# Chov2_led.net
KiCad netlist of a schematic drawn in Altium Designer
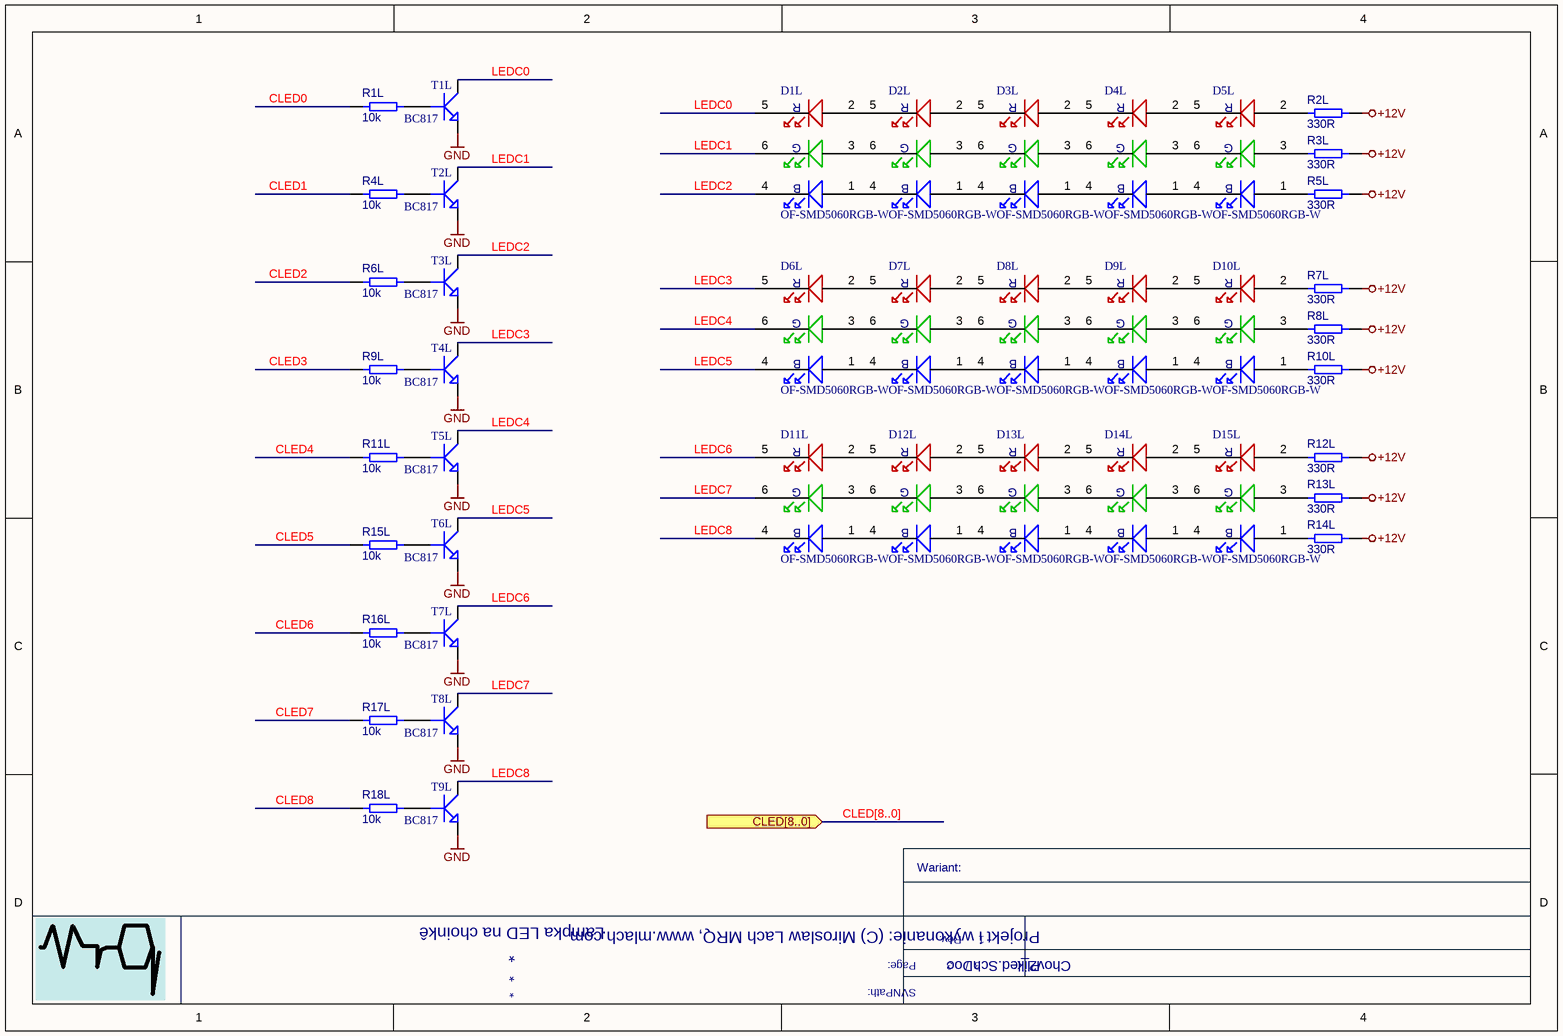
[diagram p0: Chov2_led.SchDoc]

(export (version "E")
  (design (tool "Eeschema 10.0.6"))
  (components
    (comp (ref "D1L")
      (value "OF-SMD5060RGB-W")
      (footprint "OF-SMD5060RGB-W")
      (libsource (lib "Parts") (part "OF-SMD5060RGB-W"))
    )
    (comp (ref "D2L")
      (value "OF-SMD5060RGB-W")
      (footprint "OF-SMD5060RGB-W")
      (libsource (lib "Parts") (part "OF-SMD5060RGB-W"))
    )
    (comp (ref "D3L")
      (value "OF-SMD5060RGB-W")
      (footprint "OF-SMD5060RGB-W")
      (libsource (lib "Parts") (part "OF-SMD5060RGB-W"))
    )
    (comp (ref "D4L")
      (value "OF-SMD5060RGB-W")
      (footprint "OF-SMD5060RGB-W")
      (libsource (lib "Parts") (part "OF-SMD5060RGB-W"))
    )
    (comp (ref "D5L")
      (value "OF-SMD5060RGB-W")
      (footprint "OF-SMD5060RGB-W")
      (libsource (lib "Parts") (part "OF-SMD5060RGB-W"))
    )
    (comp (ref "D6L")
      (value "OF-SMD5060RGB-W")
      (footprint "OF-SMD5060RGB-W")
      (libsource (lib "Parts") (part "OF-SMD5060RGB-W"))
    )
    (comp (ref "D7L")
      (value "OF-SMD5060RGB-W")
      (footprint "OF-SMD5060RGB-W")
      (libsource (lib "Parts") (part "OF-SMD5060RGB-W"))
    )
    (comp (ref "D8L")
      (value "OF-SMD5060RGB-W")
      (footprint "OF-SMD5060RGB-W")
      (libsource (lib "Parts") (part "OF-SMD5060RGB-W"))
    )
    (comp (ref "D9L")
      (value "OF-SMD5060RGB-W")
      (footprint "OF-SMD5060RGB-W")
      (libsource (lib "Parts") (part "OF-SMD5060RGB-W"))
    )
    (comp (ref "D10L")
      (value "OF-SMD5060RGB-W")
      (footprint "OF-SMD5060RGB-W")
      (libsource (lib "Parts") (part "OF-SMD5060RGB-W"))
    )
    (comp (ref "D11L")
      (value "OF-SMD5060RGB-W")
      (footprint "OF-SMD5060RGB-W")
      (libsource (lib "Parts") (part "OF-SMD5060RGB-W"))
    )
    (comp (ref "D12L")
      (value "OF-SMD5060RGB-W")
      (footprint "OF-SMD5060RGB-W")
      (libsource (lib "Parts") (part "OF-SMD5060RGB-W"))
    )
    (comp (ref "D13L")
      (value "OF-SMD5060RGB-W")
      (footprint "OF-SMD5060RGB-W")
      (libsource (lib "Parts") (part "OF-SMD5060RGB-W"))
    )
    (comp (ref "D14L")
      (value "OF-SMD5060RGB-W")
      (footprint "OF-SMD5060RGB-W")
      (libsource (lib "Parts") (part "OF-SMD5060RGB-W"))
    )
    (comp (ref "D15L")
      (value "OF-SMD5060RGB-W")
      (footprint "OF-SMD5060RGB-W")
      (libsource (lib "Parts") (part "OF-SMD5060RGB-W"))
    )
    (comp (ref "R1L")
      (value "0603WGF10KT5E")
      (footprint "0603-IPC")
      (fields (field (name "OTHERPARAMS") "10k") (field (name "TOLERANCE") "1%"))
      (libsource (lib "Parts") (part "R"))
    )
    (comp (ref "R2L")
      (value "0805S8F3300T5E")
      (footprint "0805")
      (fields (field (name "OTHERPARAMS") "330R") (field (name "TOLERANCE") "1%"))
      (libsource (lib "Parts") (part "R"))
    )
    (comp (ref "R3L")
      (value "0805S8F3300T5E")
      (footprint "0805")
      (fields (field (name "OTHERPARAMS") "330R") (field (name "TOLERANCE") "1%"))
      (libsource (lib "Parts") (part "R"))
    )
    (comp (ref "R4L")
      (value "0603WGF10KT5E")
      (footprint "0603-IPC")
      (fields (field (name "OTHERPARAMS") "10k") (field (name "TOLERANCE") "1%"))
      (libsource (lib "Parts") (part "R"))
    )
    (comp (ref "R5L")
      (value "0805S8F3300T5E")
      (footprint "0805")
      (fields (field (name "OTHERPARAMS") "330R") (field (name "TOLERANCE") "1%"))
      (libsource (lib "Parts") (part "R"))
    )
    (comp (ref "R6L")
      (value "0603WGF10KT5E")
      (footprint "0603-IPC")
      (fields (field (name "OTHERPARAMS") "10k") (field (name "TOLERANCE") "1%"))
      (libsource (lib "Parts") (part "R"))
    )
    (comp (ref "R7L")
      (value "0805S8F3300T5E")
      (footprint "0805")
      (fields (field (name "OTHERPARAMS") "330R") (field (name "TOLERANCE") "1%"))
      (libsource (lib "Parts") (part "R"))
    )
    (comp (ref "R8L")
      (value "0805S8F3300T5E")
      (footprint "0805")
      (fields (field (name "OTHERPARAMS") "330R") (field (name "TOLERANCE") "1%"))
      (libsource (lib "Parts") (part "R"))
    )
    (comp (ref "R9L")
      (value "0603WGF10KT5E")
      (footprint "0603-IPC")
      (fields (field (name "OTHERPARAMS") "10k") (field (name "TOLERANCE") "1%"))
      (libsource (lib "Parts") (part "R"))
    )
    (comp (ref "R10L")
      (value "0805S8F3300T5E")
      (footprint "0805")
      (fields (field (name "OTHERPARAMS") "330R") (field (name "TOLERANCE") "1%"))
      (libsource (lib "Parts") (part "R"))
    )
    (comp (ref "R11L")
      (value "0603WGF10KT5E")
      (footprint "0603-IPC")
      (fields (field (name "OTHERPARAMS") "10k") (field (name "TOLERANCE") "1%"))
      (libsource (lib "Parts") (part "R"))
    )
    (comp (ref "R12L")
      (value "0805S8F3300T5E")
      (footprint "0805")
      (fields (field (name "OTHERPARAMS") "330R") (field (name "TOLERANCE") "1%"))
      (libsource (lib "Parts") (part "R"))
    )
    (comp (ref "R13L")
      (value "0805S8F3300T5E")
      (footprint "0805")
      (fields (field (name "OTHERPARAMS") "330R") (field (name "TOLERANCE") "1%"))
      (libsource (lib "Parts") (part "R"))
    )
    (comp (ref "R14L")
      (value "0805S8F3300T5E")
      (footprint "0805")
      (fields (field (name "OTHERPARAMS") "330R") (field (name "TOLERANCE") "1%"))
      (libsource (lib "Parts") (part "R"))
    )
    (comp (ref "R15L")
      (value "0603WGF10KT5E")
      (footprint "0603-IPC")
      (fields (field (name "OTHERPARAMS") "10k") (field (name "TOLERANCE") "1%"))
      (libsource (lib "Parts") (part "R"))
    )
    (comp (ref "R16L")
      (value "0603WGF10KT5E")
      (footprint "0603-IPC")
      (fields (field (name "OTHERPARAMS") "10k") (field (name "TOLERANCE") "1%"))
      (libsource (lib "Parts") (part "R"))
    )
    (comp (ref "R17L")
      (value "0603WGF10KT5E")
      (footprint "0603-IPC")
      (fields (field (name "OTHERPARAMS") "10k") (field (name "TOLERANCE") "1%"))
      (libsource (lib "Parts") (part "R"))
    )
    (comp (ref "R18L")
      (value "0603WGF10KT5E")
      (footprint "0603-IPC")
      (fields (field (name "OTHERPARAMS") "10k") (field (name "TOLERANCE") "1%"))
      (libsource (lib "Parts") (part "R"))
    )
    (comp (ref "T1L") (value "BC817") (footprint "SOT23-3") (libsource (lib "Parts") (part "NPN_SOT23-3")))
    (comp (ref "T2L") (value "BC817") (footprint "SOT23-3") (libsource (lib "Parts") (part "NPN_SOT23-3")))
    (comp (ref "T3L") (value "BC817") (footprint "SOT23-3") (libsource (lib "Parts") (part "NPN_SOT23-3")))
    (comp (ref "T4L") (value "BC817") (footprint "SOT23-3") (libsource (lib "Parts") (part "NPN_SOT23-3")))
    (comp (ref "T5L") (value "BC817") (footprint "SOT23-3") (libsource (lib "Parts") (part "NPN_SOT23-3")))
    (comp (ref "T6L") (value "BC817") (footprint "SOT23-3") (libsource (lib "Parts") (part "NPN_SOT23-3")))
    (comp (ref "T7L") (value "BC817") (footprint "SOT23-3") (libsource (lib "Parts") (part "NPN_SOT23-3")))
    (comp (ref "T8L") (value "BC817") (footprint "SOT23-3") (libsource (lib "Parts") (part "NPN_SOT23-3")))
    (comp (ref "T9L") (value "BC817") (footprint "SOT23-3") (libsource (lib "Parts") (part "NPN_SOT23-3")))
  )
  (nets
    (net (code "1") (name "+12V") (class "Default")
      (node (ref "R10L") (pin "2") (pinfunction "2_2") (pintype "passive"))
      (node (ref "R12L") (pin "2") (pinfunction "2_2") (pintype "passive"))
      (node (ref "R13L") (pin "2") (pinfunction "2_2") (pintype "passive"))
      (node (ref "R14L") (pin "2") (pinfunction "2_2") (pintype "passive"))
      (node (ref "R2L") (pin "2") (pinfunction "2_2") (pintype "passive"))
      (node (ref "R3L") (pin "2") (pinfunction "2_2") (pintype "passive"))
      (node (ref "R5L") (pin "2") (pinfunction "2_2") (pintype "passive"))
      (node (ref "R7L") (pin "2") (pinfunction "2_2") (pintype "passive"))
      (node (ref "R8L") (pin "2") (pinfunction "2_2") (pintype "passive"))
    )
    (net (code "2") (name "/CLED0") (class "Default")
      (node (ref "R1L") (pin "1") (pinfunction "1_1") (pintype "passive"))
    )
    (net (code "3") (name "/CLED1") (class "Default")
      (node (ref "R4L") (pin "1") (pinfunction "1_1") (pintype "passive"))
    )
    (net (code "4") (name "/CLED2") (class "Default")
      (node (ref "R6L") (pin "1") (pinfunction "1_1") (pintype "passive"))
    )
    (net (code "5") (name "/CLED3") (class "Default")
      (node (ref "R9L") (pin "1") (pinfunction "1_1") (pintype "passive"))
    )
    (net (code "6") (name "/CLED4") (class "Default")
      (node (ref "R11L") (pin "1") (pinfunction "1_1") (pintype "passive"))
    )
    (net (code "7") (name "/CLED5") (class "Default")
      (node (ref "R15L") (pin "1") (pinfunction "1_1") (pintype "passive"))
    )
    (net (code "8") (name "/CLED6") (class "Default")
      (node (ref "R16L") (pin "1") (pinfunction "1_1") (pintype "passive"))
    )
    (net (code "9") (name "/CLED7") (class "Default")
      (node (ref "R17L") (pin "1") (pinfunction "1_1") (pintype "passive"))
    )
    (net (code "10") (name "/CLED8") (class "Default")
      (node (ref "R18L") (pin "1") (pinfunction "1_1") (pintype "passive"))
    )
    (net (code "12") (name "/LEDC0") (class "Default")
      (node (ref "D1L") (pin "5") (pinfunction "CATH_5") (pintype "passive"))
      (node (ref "T1L") (pin "3") (pinfunction "3_3") (pintype "passive"))
    )
    (net (code "13") (name "/LEDC1") (class "Default")
      (node (ref "D1L") (pin "6") (pinfunction "CATH_6") (pintype "passive"))
      (node (ref "T2L") (pin "3") (pinfunction "3_3") (pintype "passive"))
    )
    (net (code "14") (name "/LEDC2") (class "Default")
      (node (ref "D1L") (pin "4") (pinfunction "CATH_4") (pintype "passive"))
      (node (ref "T3L") (pin "3") (pinfunction "3_3") (pintype "passive"))
    )
    (net (code "15") (name "/LEDC3") (class "Default")
      (node (ref "D6L") (pin "5") (pinfunction "CATH_5") (pintype "passive"))
      (node (ref "T4L") (pin "3") (pinfunction "3_3") (pintype "passive"))
    )
    (net (code "16") (name "/LEDC4") (class "Default")
      (node (ref "D6L") (pin "6") (pinfunction "CATH_6") (pintype "passive"))
      (node (ref "T5L") (pin "3") (pinfunction "3_3") (pintype "passive"))
    )
    (net (code "17") (name "/LEDC5") (class "Default")
      (node (ref "D6L") (pin "4") (pinfunction "CATH_4") (pintype "passive"))
      (node (ref "T6L") (pin "3") (pinfunction "3_3") (pintype "passive"))
    )
    (net (code "18") (name "/LEDC6") (class "Default")
      (node (ref "D11L") (pin "5") (pinfunction "CATH_5") (pintype "passive"))
      (node (ref "T7L") (pin "3") (pinfunction "3_3") (pintype "passive"))
    )
    (net (code "19") (name "/LEDC7") (class "Default")
      (node (ref "D11L") (pin "6") (pinfunction "CATH_6") (pintype "passive"))
      (node (ref "T8L") (pin "3") (pinfunction "3_3") (pintype "passive"))
    )
    (net (code "20") (name "/LEDC8") (class "Default")
      (node (ref "D11L") (pin "4") (pinfunction "CATH_4") (pintype "passive"))
      (node (ref "T9L") (pin "3") (pinfunction "3_3") (pintype "passive"))
    )
    (net (code "21") (name "GND") (class "Default")
      (node (ref "T1L") (pin "2") (pinfunction "2_2") (pintype "passive"))
      (node (ref "T2L") (pin "2") (pinfunction "2_2") (pintype "passive"))
      (node (ref "T3L") (pin "2") (pinfunction "2_2") (pintype "passive"))
      (node (ref "T4L") (pin "2") (pinfunction "2_2") (pintype "passive"))
      (node (ref "T5L") (pin "2") (pinfunction "2_2") (pintype "passive"))
      (node (ref "T6L") (pin "2") (pinfunction "2_2") (pintype "passive"))
      (node (ref "T7L") (pin "2") (pinfunction "2_2") (pintype "passive"))
      (node (ref "T8L") (pin "2") (pinfunction "2_2") (pintype "passive"))
      (node (ref "T9L") (pin "2") (pinfunction "2_2") (pintype "passive"))
    )
    (net (code "22") (name "Net-(D1L-ANOD-Pad1)") (class "Default")
      (node (ref "D1L") (pin "1") (pinfunction "ANOD_1") (pintype "passive"))
      (node (ref "D2L") (pin "4") (pinfunction "CATH_4") (pintype "passive"))
    )
    (net (code "23") (name "Net-(D1L-ANOD-Pad2)") (class "Default")
      (node (ref "D1L") (pin "2") (pinfunction "ANOD_2") (pintype "passive"))
      (node (ref "D2L") (pin "5") (pinfunction "CATH_5") (pintype "passive"))
    )
    (net (code "24") (name "Net-(D1L-ANOD-Pad3)") (class "Default")
      (node (ref "D1L") (pin "3") (pinfunction "ANOD_3") (pintype "passive"))
      (node (ref "D2L") (pin "6") (pinfunction "CATH_6") (pintype "passive"))
    )
    (net (code "25") (name "Net-(D2L-ANOD-Pad1)") (class "Default")
      (node (ref "D2L") (pin "1") (pinfunction "ANOD_1") (pintype "passive"))
      (node (ref "D3L") (pin "4") (pinfunction "CATH_4") (pintype "passive"))
    )
    (net (code "26") (name "Net-(D2L-ANOD-Pad2)") (class "Default")
      (node (ref "D2L") (pin "2") (pinfunction "ANOD_2") (pintype "passive"))
      (node (ref "D3L") (pin "5") (pinfunction "CATH_5") (pintype "passive"))
    )
    (net (code "27") (name "Net-(D2L-ANOD-Pad3)") (class "Default")
      (node (ref "D2L") (pin "3") (pinfunction "ANOD_3") (pintype "passive"))
      (node (ref "D3L") (pin "6") (pinfunction "CATH_6") (pintype "passive"))
    )
    (net (code "28") (name "Net-(D3L-ANOD-Pad1)") (class "Default")
      (node (ref "D3L") (pin "1") (pinfunction "ANOD_1") (pintype "passive"))
      (node (ref "D4L") (pin "4") (pinfunction "CATH_4") (pintype "passive"))
    )
    (net (code "29") (name "Net-(D3L-ANOD-Pad2)") (class "Default")
      (node (ref "D3L") (pin "2") (pinfunction "ANOD_2") (pintype "passive"))
      (node (ref "D4L") (pin "5") (pinfunction "CATH_5") (pintype "passive"))
    )
    (net (code "30") (name "Net-(D3L-ANOD-Pad3)") (class "Default")
      (node (ref "D3L") (pin "3") (pinfunction "ANOD_3") (pintype "passive"))
      (node (ref "D4L") (pin "6") (pinfunction "CATH_6") (pintype "passive"))
    )
    (net (code "31") (name "Net-(D4L-ANOD-Pad1)") (class "Default")
      (node (ref "D4L") (pin "1") (pinfunction "ANOD_1") (pintype "passive"))
      (node (ref "D5L") (pin "4") (pinfunction "CATH_4") (pintype "passive"))
    )
    (net (code "32") (name "Net-(D4L-ANOD-Pad2)") (class "Default")
      (node (ref "D4L") (pin "2") (pinfunction "ANOD_2") (pintype "passive"))
      (node (ref "D5L") (pin "5") (pinfunction "CATH_5") (pintype "passive"))
    )
    (net (code "33") (name "Net-(D4L-ANOD-Pad3)") (class "Default")
      (node (ref "D4L") (pin "3") (pinfunction "ANOD_3") (pintype "passive"))
      (node (ref "D5L") (pin "6") (pinfunction "CATH_6") (pintype "passive"))
    )
    (net (code "34") (name "Net-(D5L-ANOD-Pad1)") (class "Default")
      (node (ref "D5L") (pin "1") (pinfunction "ANOD_1") (pintype "passive"))
      (node (ref "R5L") (pin "1") (pinfunction "1_1") (pintype "passive"))
    )
    (net (code "35") (name "Net-(D5L-ANOD-Pad2)") (class "Default")
      (node (ref "D5L") (pin "2") (pinfunction "ANOD_2") (pintype "passive"))
      (node (ref "R2L") (pin "1") (pinfunction "1_1") (pintype "passive"))
    )
    (net (code "36") (name "Net-(D5L-ANOD-Pad3)") (class "Default")
      (node (ref "D5L") (pin "3") (pinfunction "ANOD_3") (pintype "passive"))
      (node (ref "R3L") (pin "1") (pinfunction "1_1") (pintype "passive"))
    )
    (net (code "37") (name "Net-(D6L-ANOD-Pad1)") (class "Default")
      (node (ref "D6L") (pin "1") (pinfunction "ANOD_1") (pintype "passive"))
      (node (ref "D7L") (pin "4") (pinfunction "CATH_4") (pintype "passive"))
    )
    (net (code "38") (name "Net-(D6L-ANOD-Pad2)") (class "Default")
      (node (ref "D6L") (pin "2") (pinfunction "ANOD_2") (pintype "passive"))
      (node (ref "D7L") (pin "5") (pinfunction "CATH_5") (pintype "passive"))
    )
    (net (code "39") (name "Net-(D6L-ANOD-Pad3)") (class "Default")
      (node (ref "D6L") (pin "3") (pinfunction "ANOD_3") (pintype "passive"))
      (node (ref "D7L") (pin "6") (pinfunction "CATH_6") (pintype "passive"))
    )
    (net (code "40") (name "Net-(D7L-ANOD-Pad1)") (class "Default")
      (node (ref "D7L") (pin "1") (pinfunction "ANOD_1") (pintype "passive"))
      (node (ref "D8L") (pin "4") (pinfunction "CATH_4") (pintype "passive"))
    )
    (net (code "41") (name "Net-(D7L-ANOD-Pad2)") (class "Default")
      (node (ref "D7L") (pin "2") (pinfunction "ANOD_2") (pintype "passive"))
      (node (ref "D8L") (pin "5") (pinfunction "CATH_5") (pintype "passive"))
    )
    (net (code "42") (name "Net-(D7L-ANOD-Pad3)") (class "Default")
      (node (ref "D7L") (pin "3") (pinfunction "ANOD_3") (pintype "passive"))
      (node (ref "D8L") (pin "6") (pinfunction "CATH_6") (pintype "passive"))
    )
    (net (code "43") (name "Net-(D8L-ANOD-Pad1)") (class "Default")
      (node (ref "D8L") (pin "1") (pinfunction "ANOD_1") (pintype "passive"))
      (node (ref "D9L") (pin "4") (pinfunction "CATH_4") (pintype "passive"))
    )
    (net (code "44") (name "Net-(D8L-ANOD-Pad2)") (class "Default")
      (node (ref "D8L") (pin "2") (pinfunction "ANOD_2") (pintype "passive"))
      (node (ref "D9L") (pin "5") (pinfunction "CATH_5") (pintype "passive"))
    )
    (net (code "45") (name "Net-(D8L-ANOD-Pad3)") (class "Default")
      (node (ref "D8L") (pin "3") (pinfunction "ANOD_3") (pintype "passive"))
      (node (ref "D9L") (pin "6") (pinfunction "CATH_6") (pintype "passive"))
    )
    (net (code "46") (name "Net-(D10L-ANOD-Pad1)") (class "Default")
      (node (ref "D10L") (pin "1") (pinfunction "ANOD_1") (pintype "passive"))
      (node (ref "R10L") (pin "1") (pinfunction "1_1") (pintype "passive"))
    )
    (net (code "47") (name "Net-(D10L-ANOD-Pad2)") (class "Default")
      (node (ref "D10L") (pin "2") (pinfunction "ANOD_2") (pintype "passive"))
      (node (ref "R7L") (pin "1") (pinfunction "1_1") (pintype "passive"))
    )
    (net (code "48") (name "Net-(D10L-ANOD-Pad3)") (class "Default")
      (node (ref "D10L") (pin "3") (pinfunction "ANOD_3") (pintype "passive"))
      (node (ref "R8L") (pin "1") (pinfunction "1_1") (pintype "passive"))
    )
    (net (code "49") (name "Net-(D10L-CATH-Pad4)") (class "Default")
      (node (ref "D10L") (pin "4") (pinfunction "CATH_4") (pintype "passive"))
      (node (ref "D9L") (pin "1") (pinfunction "ANOD_1") (pintype "passive"))
    )
    (net (code "50") (name "Net-(D10L-CATH-Pad5)") (class "Default")
      (node (ref "D10L") (pin "5") (pinfunction "CATH_5") (pintype "passive"))
      (node (ref "D9L") (pin "2") (pinfunction "ANOD_2") (pintype "passive"))
    )
    (net (code "51") (name "Net-(D10L-CATH-Pad6)") (class "Default")
      (node (ref "D10L") (pin "6") (pinfunction "CATH_6") (pintype "passive"))
      (node (ref "D9L") (pin "3") (pinfunction "ANOD_3") (pintype "passive"))
    )
    (net (code "52") (name "Net-(D11L-ANOD-Pad1)") (class "Default")
      (node (ref "D11L") (pin "1") (pinfunction "ANOD_1") (pintype "passive"))
      (node (ref "D12L") (pin "4") (pinfunction "CATH_4") (pintype "passive"))
    )
    (net (code "53") (name "Net-(D11L-ANOD-Pad2)") (class "Default")
      (node (ref "D11L") (pin "2") (pinfunction "ANOD_2") (pintype "passive"))
      (node (ref "D12L") (pin "5") (pinfunction "CATH_5") (pintype "passive"))
    )
    (net (code "54") (name "Net-(D11L-ANOD-Pad3)") (class "Default")
      (node (ref "D11L") (pin "3") (pinfunction "ANOD_3") (pintype "passive"))
      (node (ref "D12L") (pin "6") (pinfunction "CATH_6") (pintype "passive"))
    )
    (net (code "55") (name "Net-(D12L-ANOD-Pad1)") (class "Default")
      (node (ref "D12L") (pin "1") (pinfunction "ANOD_1") (pintype "passive"))
      (node (ref "D13L") (pin "4") (pinfunction "CATH_4") (pintype "passive"))
    )
    (net (code "56") (name "Net-(D12L-ANOD-Pad2)") (class "Default")
      (node (ref "D12L") (pin "2") (pinfunction "ANOD_2") (pintype "passive"))
      (node (ref "D13L") (pin "5") (pinfunction "CATH_5") (pintype "passive"))
    )
    (net (code "57") (name "Net-(D12L-ANOD-Pad3)") (class "Default")
      (node (ref "D12L") (pin "3") (pinfunction "ANOD_3") (pintype "passive"))
      (node (ref "D13L") (pin "6") (pinfunction "CATH_6") (pintype "passive"))
    )
    (net (code "58") (name "Net-(D13L-ANOD-Pad1)") (class "Default")
      (node (ref "D13L") (pin "1") (pinfunction "ANOD_1") (pintype "passive"))
      (node (ref "D14L") (pin "4") (pinfunction "CATH_4") (pintype "passive"))
    )
    (net (code "59") (name "Net-(D13L-ANOD-Pad2)") (class "Default")
      (node (ref "D13L") (pin "2") (pinfunction "ANOD_2") (pintype "passive"))
      (node (ref "D14L") (pin "5") (pinfunction "CATH_5") (pintype "passive"))
    )
    (net (code "60") (name "Net-(D13L-ANOD-Pad3)") (class "Default")
      (node (ref "D13L") (pin "3") (pinfunction "ANOD_3") (pintype "passive"))
      (node (ref "D14L") (pin "6") (pinfunction "CATH_6") (pintype "passive"))
    )
    (net (code "61") (name "Net-(D14L-ANOD-Pad1)") (class "Default")
      (node (ref "D14L") (pin "1") (pinfunction "ANOD_1") (pintype "passive"))
      (node (ref "D15L") (pin "4") (pinfunction "CATH_4") (pintype "passive"))
    )
    (net (code "62") (name "Net-(D14L-ANOD-Pad2)") (class "Default")
      (node (ref "D14L") (pin "2") (pinfunction "ANOD_2") (pintype "passive"))
      (node (ref "D15L") (pin "5") (pinfunction "CATH_5") (pintype "passive"))
    )
    (net (code "63") (name "Net-(D14L-ANOD-Pad3)") (class "Default")
      (node (ref "D14L") (pin "3") (pinfunction "ANOD_3") (pintype "passive"))
      (node (ref "D15L") (pin "6") (pinfunction "CATH_6") (pintype "passive"))
    )
    (net (code "64") (name "Net-(D15L-ANOD-Pad1)") (class "Default")
      (node (ref "D15L") (pin "1") (pinfunction "ANOD_1") (pintype "passive"))
      (node (ref "R14L") (pin "1") (pinfunction "1_1") (pintype "passive"))
    )
    (net (code "65") (name "Net-(D15L-ANOD-Pad2)") (class "Default")
      (node (ref "D15L") (pin "2") (pinfunction "ANOD_2") (pintype "passive"))
      (node (ref "R12L") (pin "1") (pinfunction "1_1") (pintype "passive"))
    )
    (net (code "66") (name "Net-(D15L-ANOD-Pad3)") (class "Default")
      (node (ref "D15L") (pin "3") (pinfunction "ANOD_3") (pintype "passive"))
      (node (ref "R13L") (pin "1") (pinfunction "1_1") (pintype "passive"))
    )
    (net (code "67") (name "Net-(R1L-Pad2)") (class "Default")
      (node (ref "R1L") (pin "2") (pinfunction "2_2") (pintype "passive"))
      (node (ref "T1L") (pin "1") (pinfunction "1_1") (pintype "passive"))
    )
    (net (code "68") (name "Net-(R4L-Pad2)") (class "Default")
      (node (ref "R4L") (pin "2") (pinfunction "2_2") (pintype "passive"))
      (node (ref "T2L") (pin "1") (pinfunction "1_1") (pintype "passive"))
    )
    (net (code "69") (name "Net-(R6L-Pad2)") (class "Default")
      (node (ref "R6L") (pin "2") (pinfunction "2_2") (pintype "passive"))
      (node (ref "T3L") (pin "1") (pinfunction "1_1") (pintype "passive"))
    )
    (net (code "70") (name "Net-(R9L-Pad2)") (class "Default")
      (node (ref "R9L") (pin "2") (pinfunction "2_2") (pintype "passive"))
      (node (ref "T4L") (pin "1") (pinfunction "1_1") (pintype "passive"))
    )
    (net (code "71") (name "Net-(R11L-Pad2)") (class "Default")
      (node (ref "R11L") (pin "2") (pinfunction "2_2") (pintype "passive"))
      (node (ref "T5L") (pin "1") (pinfunction "1_1") (pintype "passive"))
    )
    (net (code "72") (name "Net-(R15L-Pad2)") (class "Default")
      (node (ref "R15L") (pin "2") (pinfunction "2_2") (pintype "passive"))
      (node (ref "T6L") (pin "1") (pinfunction "1_1") (pintype "passive"))
    )
    (net (code "73") (name "Net-(R16L-Pad2)") (class "Default")
      (node (ref "R16L") (pin "2") (pinfunction "2_2") (pintype "passive"))
      (node (ref "T7L") (pin "1") (pinfunction "1_1") (pintype "passive"))
    )
    (net (code "74") (name "Net-(R17L-Pad2)") (class "Default")
      (node (ref "R17L") (pin "2") (pinfunction "2_2") (pintype "passive"))
      (node (ref "T8L") (pin "1") (pinfunction "1_1") (pintype "passive"))
    )
    (net (code "75") (name "Net-(R18L-Pad2)") (class "Default")
      (node (ref "R18L") (pin "2") (pinfunction "2_2") (pintype "passive"))
      (node (ref "T9L") (pin "1") (pinfunction "1_1") (pintype "passive"))
    )
  )
)
